# internet_access.net
KiCad netlist of a schematic drawn in Altium Designer
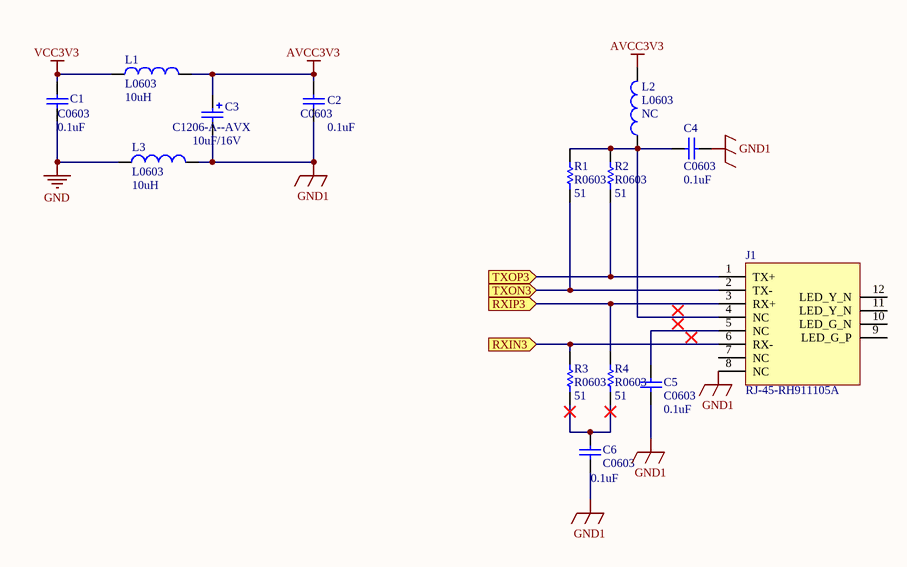
[diagram p0: internet access.SchDoc]

(export (version "E")
  (design (tool "Eeschema 10.0.6"))
  (components
    (comp (ref "C1")
      (value "C0603")
      (footprint "C0603N")
      (description "Capacitor (Semiconductor SIM Model)")
      (fields (field (name "ALTIUM_VALUE") "0.1uF"))
      (libsource (lib "schumyhao's_Device") (part "Cap Semi"))
    )
    (comp (ref "C2")
      (value "C0603")
      (footprint "C0603N")
      (description "Capacitor (Semiconductor SIM Model)")
      (fields (field (name "ALTIUM_VALUE") "0.1uF"))
      (libsource (lib "schumyhao's_Device") (part "Cap Semi"))
    )
    (comp (ref "C3")
      (value "C1206-A--AVX")
      (footprint "C1206-A")
      (description "Polarized Capacitor (Surface Mount)")
      (fields (field (name "ALTIUM_VALUE") "10uF/16V"))
      (libsource (lib "schumyhao's_Device") (part "Cap Pol3"))
    )
    (comp (ref "C4")
      (value "C0603")
      (footprint "C0603N")
      (description "Capacitor (Semiconductor SIM Model)")
      (fields (field (name "ALTIUM_VALUE") "0.1uF"))
      (libsource (lib "schumyhao's_Device") (part "Cap Semi"))
    )
    (comp (ref "C5")
      (value "C0603")
      (footprint "C0603N")
      (description "Capacitor (Semiconductor SIM Model)")
      (fields (field (name "ALTIUM_VALUE") "0.1uF"))
      (libsource (lib "schumyhao's_Device") (part "Cap Semi"))
    )
    (comp (ref "C6")
      (value "C0603")
      (footprint "C0603N")
      (description "Capacitor (Semiconductor SIM Model)")
      (fields (field (name "ALTIUM_VALUE") "0.1uF"))
      (libsource (lib "schumyhao's_Device") (part "Cap Semi"))
    )
    (comp (ref "J1")
      (value "RJ-45-RH911105A")
      (footprint "RJ-45-HR911105A")
      (libsource (lib "schumyhao's_Device") (part "RJ-45-RH911105A"))
    )
    (comp (ref "L1")
      (value "L0603")
      (footprint "C0603N")
      (description "Inductor")
      (fields (field (name "ALTIUM_VALUE") "10uH"))
      (libsource (lib "schumyhao's_Device") (part "Inductor"))
    )
    (comp (ref "L2")
      (value "L0603")
      (footprint "C0603N")
      (description "Inductor")
      (fields (field (name "ALTIUM_VALUE") "NC"))
      (libsource (lib "schumyhao's_Device") (part "Inductor"))
    )
    (comp (ref "L3")
      (value "L0603")
      (footprint "C0603N")
      (description "Inductor")
      (fields (field (name "ALTIUM_VALUE") "10uH"))
      (libsource (lib "schumyhao's_Device") (part "Inductor"))
    )
    (comp (ref "R1")
      (value "R0603")
      (footprint "R0603N")
      (description "Semiconductor Resistor")
      (fields (field (name "ALTIUM_VALUE") "51"))
      (libsource (lib "schumyhao's_Device") (part "Res Semi"))
    )
    (comp (ref "R2")
      (value "R0603")
      (footprint "R0603N")
      (description "Semiconductor Resistor")
      (fields (field (name "ALTIUM_VALUE") "51"))
      (libsource (lib "schumyhao's_Device") (part "Res Semi"))
    )
    (comp (ref "R3")
      (value "R0603")
      (footprint "R0603N")
      (description "Semiconductor Resistor")
      (fields (field (name "ALTIUM_VALUE") "51"))
      (libsource (lib "schumyhao's_Device") (part "Res Semi"))
    )
    (comp (ref "R4")
      (value "R0603")
      (footprint "R0603N")
      (description "Semiconductor Resistor")
      (fields (field (name "ALTIUM_VALUE") "51"))
      (libsource (lib "schumyhao's_Device") (part "Res Semi"))
    )
  )
  (nets
    (net (code "1") (name "/RXIN3") (class "Default")
      (node (ref "J1") (pin "6") (pinfunction "RX-_6") (pintype "passive"))
      (node (ref "R3") (pin "2") (pinfunction "2_2") (pintype "passive"))
    )
    (net (code "2") (name "/RXIP3") (class "Default")
      (node (ref "J1") (pin "3") (pinfunction "RX+_3") (pintype "passive"))
      (node (ref "R4") (pin "2") (pinfunction "2_2") (pintype "passive"))
    )
    (net (code "3") (name "/TXON3") (class "Default")
      (node (ref "J1") (pin "2") (pinfunction "TX-_2") (pintype "passive"))
      (node (ref "R1") (pin "1") (pinfunction "1_1") (pintype "passive"))
    )
    (net (code "4") (name "/TXOP3") (class "Default")
      (node (ref "J1") (pin "1") (pinfunction "TX+_1") (pintype "passive"))
      (node (ref "R2") (pin "1") (pinfunction "1_1") (pintype "passive"))
    )
    (net (code "5") (name "AVCC3V3") (class "Default")
      (node (ref "C2") (pin "1") (pinfunction "1_1") (pintype "passive"))
      (node (ref "C3") (pin "1") (pinfunction "1_1") (pintype "passive"))
      (node (ref "L1") (pin "2") (pinfunction "2_2") (pintype "passive"))
      (node (ref "L2") (pin "2") (pinfunction "2_2") (pintype "passive"))
    )
    (net (code "6") (name "GND") (class "Default")
      (node (ref "C1") (pin "2") (pinfunction "2_2") (pintype "passive"))
      (node (ref "L3") (pin "1") (pinfunction "1_1") (pintype "passive"))
    )
    (net (code "7") (name "GND1") (class "Default")
      (node (ref "C2") (pin "2") (pinfunction "2_2") (pintype "passive"))
      (node (ref "C3") (pin "2") (pinfunction "2_2") (pintype "passive"))
      (node (ref "C4") (pin "2") (pinfunction "2_2") (pintype "passive"))
      (node (ref "C5") (pin "1") (pinfunction "1_1") (pintype "passive"))
      (node (ref "C6") (pin "1") (pinfunction "1_1") (pintype "passive"))
      (node (ref "J1") (pin "8") (pinfunction "NC_8") (pintype "passive"))
      (node (ref "L3") (pin "2") (pinfunction "2_2") (pintype "passive"))
    )
    (net (code "8") (name "Net-(C4-Pad1)") (class "Default")
      (node (ref "C4") (pin "1") (pinfunction "1_1") (pintype "passive"))
      (node (ref "J1") (pin "4") (pinfunction "NC_4") (pintype "passive"))
      (node (ref "L2") (pin "1") (pinfunction "1_1") (pintype "passive"))
      (node (ref "R1") (pin "2") (pinfunction "2_2") (pintype "passive"))
      (node (ref "R2") (pin "2") (pinfunction "2_2") (pintype "passive"))
    )
    (net (code "9") (name "Net-(C5-Pad2)") (class "Default")
      (node (ref "C5") (pin "2") (pinfunction "2_2") (pintype "passive"))
      (node (ref "J1") (pin "5") (pinfunction "NC_5") (pintype "passive"))
    )
    (net (code "10") (name "Net-(C6-Pad2)") (class "Default")
      (node (ref "C6") (pin "2") (pinfunction "2_2") (pintype "passive"))
      (node (ref "R3") (pin "1") (pinfunction "1_1") (pintype "passive"))
      (node (ref "R4") (pin "1") (pinfunction "1_1") (pintype "passive"))
    )
    (net (code "11") (name "VCC3V3") (class "Default")
      (node (ref "C1") (pin "1") (pinfunction "1_1") (pintype "passive"))
      (node (ref "L1") (pin "1") (pinfunction "1_1") (pintype "passive"))
    )
    (net (code "12") (name "unconnected-(J1-LED_G_N-Pad10)") (class "Default")
      (node (ref "J1") (pin "10") (pinfunction "LED_G_N_10") (pintype "passive"))
    )
    (net (code "13") (name "unconnected-(J1-LED_G_P-Pad9)") (class "Default")
      (node (ref "J1") (pin "9") (pinfunction "LED_G_P_9") (pintype "passive"))
    )
    (net (code "14") (name "unconnected-(J1-LED_Y_N-Pad11)") (class "Default")
      (node (ref "J1") (pin "11") (pinfunction "LED_Y_N_11") (pintype "passive"))
    )
    (net (code "15") (name "unconnected-(J1-LED_Y_N-Pad12)") (class "Default")
      (node (ref "J1") (pin "12") (pinfunction "LED_Y_N_12") (pintype "passive"))
    )
    (net (code "16") (name "unconnected-(J1-NC-Pad7)") (class "Default")
      (node (ref "J1") (pin "7") (pinfunction "NC_7") (pintype "passive"))
    )
  )
)
